# 1_-Power.net
KiCad netlist of a schematic drawn in Altium Designer
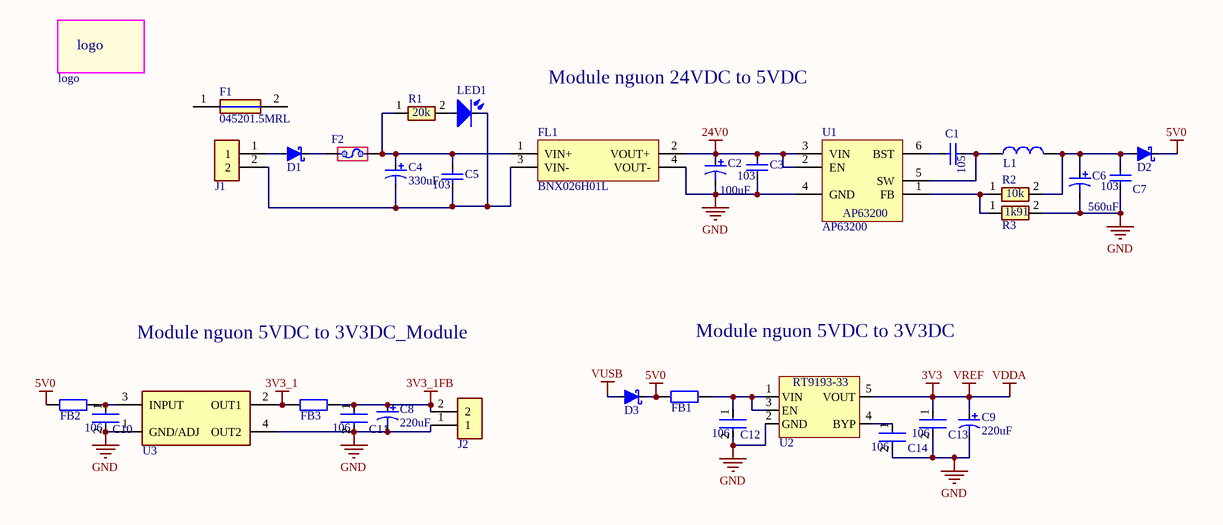
[diagram p0: [1]-Power.SchDoc]

(export (version "E")
  (design (tool "Eeschema 10.0.6"))
  (components
    (comp (ref "1")
      (value "logo")
      (footprint "SamacSys:logo_new_10mm")
      (libsource (lib "SamacSys") (part "logo"))
    )
    (comp (ref "C1")
      (value "C0603_105_50V")
      (footprint "SamacSys:C0603")
      (description "Multilayer Ceramic Capacitors MLCC - SMD/SMT 50 V 1uF X7R 0603 10%")
      (fields
        (field (name "MANUFACTURER_PART_NUMBER") "CC0603KRX7R9BB105")
        (field (name "MOUSER PART NUMBER") "603-CC603KRX7R9BB105")
      )
      (libsource (lib "SamacSys") (part "C0603_105_50V"))
    )
    (comp (ref "C2")
      (value "100uF")
      (footprint "SamacSys:CAP_ALUM_6_5x6_5")
      (description "Capacitor Polarised")
      (fields
        (field (name "MANUFACTURER_PART_NUMBER") "EEH-ZK1V101XP")
        (field (name "MOUSER PART NUMBER") "667-EEH-ZK1V101XP")
      )
      (libsource (lib "SamacSys") (part "C_Al_100uF_35V"))
    )
    (comp (ref "C3")
      (value "C0603_103_50V")
      (footprint "SamacSys:C0603")
      (description "Multilayer Ceramic Capacitors MLCC - SMD/SMT 50V 0.01uF X7R 0603 10%")
      (fields
        (field (name "MANUFACTURER_PART_NUMBER") "CC0603KRX7R9BB103")
        (field (name "MOUSER PART NUMBER") "603-CC603KRX7R9BB103")
      )
      (libsource (lib "SamacSys") (part "C0603_103_50V"))
    )
    (comp (ref "C4")
      (value "330uF")
      (footprint "CAP_ALUM_10X10")
      (description "Aluminum Organic Polymer Capacitors 35Vol 330uF SMD 2KHr ESR=22 mOhms AECQ200")
      (fields
        (field (name "MANUFACTURER_PART_NUMBER") "A768MS337M1VLAS022")
        (field (name "MOUSER PART NUMBER") "80-A768MS337M1VLAS22")
      )
      (libsource (lib "SamacSys") (part "C_Al_330uF_35V"))
    )
    (comp (ref "C5")
      (value "C0603_103_50V")
      (footprint "SamacSys:C0603")
      (description "Multilayer Ceramic Capacitors MLCC - SMD/SMT 50V 0.01uF X7R 0603 10%")
      (fields
        (field (name "MANUFACTURER_PART_NUMBER") "CC0603KRX7R9BB103")
        (field (name "MOUSER PART NUMBER") "603-CC603KRX7R9BB103")
      )
      (libsource (lib "SamacSys") (part "C0603_103_50V"))
    )
    (comp (ref "C6")
      (value "560uF")
      (footprint "SamacSys:CAP_ALUM_6_5x6_5")
      (description "560 µF 6.3 V Aluminum - Polymer Capacitors Radial, Can - SMD 8mOhm 15000 Hrs @ 105°C")
      (fields
        (field (name "MANUFACTURER") "United Chemi-Con")
        (field (name "PART NUMBER") "APXJ6R3ARA561MF80G")
      )
      (libsource (lib "SamacSys") (part "CAP_ALU6.3_560uF_6.3V"))
    )
    (comp (ref "C7")
      (value "C0603_103_50V")
      (footprint "SamacSys:C0603")
      (description "Multilayer Ceramic Capacitors MLCC - SMD/SMT 50V 0.01uF X7R 0603 10%")
      (fields
        (field (name "MANUFACTURER_PART_NUMBER") "CC0603KRX7R9BB103")
        (field (name "MOUSER PART NUMBER") "603-CC603KRX7R9BB103")
      )
      (libsource (lib "SamacSys") (part "C0603_103_50V"))
    )
    (comp (ref "C8")
      (value "220uF")
      (footprint "SamacSys:CAP_TAN_7343")
      (description "220 µF Molded Tantalum Capacitors 16 V 2917 (7343 Metric) 25mOhm")
      (fields (field (name "MANUFACTURER") "KYOCERA AVX") (field (name "PART NUMBER") "TPME227K016R0025"))
      (libsource (lib "SamacSys") (part "CAP_TAN_7343_220uF_16V"))
    )
    (comp (ref "C9")
      (value "220uF")
      (footprint "SamacSys:CAP_TAN_7343")
      (description "220 µF Molded Tantalum Capacitors 16 V 2917 (7343 Metric) 25mOhm")
      (fields (field (name "MANUFACTURER") "KYOCERA AVX") (field (name "PART NUMBER") "TPME227K016R0025"))
      (libsource (lib "SamacSys") (part "CAP_TAN_7343_220uF_16V"))
    )
    (comp (ref "C10")
      (value "C0603_106_35V")
      (footprint "SamacSys:C0603")
      (description "Multilayer Ceramic Capacitors MLCC - SMD/SMT 10 uF 35 VDC 20% 0603 X5R")
      (fields
        (field (name "MANUFACTURER_PART_NUMBER") "GRM188R6YA106MA73J")
        (field (name "MOUSER PART NUMBER") "81-GRM188R6YA106MA3J")
      )
      (libsource (lib "SamacSys") (part "C0603_106_35V"))
    )
    (comp (ref "C11")
      (value "C0603_106_35V")
      (footprint "SamacSys:C0603")
      (description "Multilayer Ceramic Capacitors MLCC - SMD/SMT 10 uF 35 VDC 20% 0603 X5R")
      (fields
        (field (name "MANUFACTURER_PART_NUMBER") "GRM188R6YA106MA73J")
        (field (name "MOUSER PART NUMBER") "81-GRM188R6YA106MA3J")
      )
      (libsource (lib "SamacSys") (part "C0603_106_35V"))
    )
    (comp (ref "C12")
      (value "C0603_106_35V")
      (footprint "SamacSys:C0603")
      (description "Multilayer Ceramic Capacitors MLCC - SMD/SMT 10 uF 35 VDC 20% 0603 X5R")
      (fields
        (field (name "MANUFACTURER_PART_NUMBER") "GRM188R6YA106MA73J")
        (field (name "MOUSER PART NUMBER") "81-GRM188R6YA106MA3J")
      )
      (libsource (lib "SamacSys") (part "C0603_106_35V"))
    )
    (comp (ref "C13")
      (value "C0603_106_35V")
      (footprint "SamacSys:C0603")
      (description "Multilayer Ceramic Capacitors MLCC - SMD/SMT 10 uF 35 VDC 20% 0603 X5R")
      (fields
        (field (name "MANUFACTURER_PART_NUMBER") "GRM188R6YA106MA73J")
        (field (name "MOUSER PART NUMBER") "81-GRM188R6YA106MA3J")
      )
      (libsource (lib "SamacSys") (part "C0603_106_35V"))
    )
    (comp (ref "C14")
      (value "C0603_106_35V")
      (footprint "SamacSys:C0603")
      (description "Multilayer Ceramic Capacitors MLCC - SMD/SMT 10 uF 35 VDC 20% 0603 X5R")
      (fields
        (field (name "MANUFACTURER_PART_NUMBER") "GRM188R6YA106MA73J")
        (field (name "MOUSER PART NUMBER") "81-GRM188R6YA106MA3J")
      )
      (libsource (lib "SamacSys") (part "C0603_106_35V"))
    )
    (comp (ref "D1")
      (value "PMEG40T30ERX")
      (footprint "SamacSys:SOD123")
      (description "Schottky Diode 40V 3A")
      (fields (field (name "MOUSER PART NUMBER") "771-PMEG40T30ERX"))
      (libsource (lib "SamacSys") (part "PMEG40T30ERX"))
    )
    (comp (ref "D2")
      (value "PMEG40T30ERX")
      (footprint "SamacSys:SOD123")
      (description "Schottky Diode 40V 3A")
      (fields (field (name "MOUSER PART NUMBER") "771-PMEG40T30ERX"))
      (libsource (lib "SamacSys") (part "PMEG40T30ERX"))
    )
    (comp (ref "D3")
      (value "PMEG40T30ERX")
      (footprint "SamacSys:SOD123")
      (description "Schottky Diode 40V 3A")
      (fields (field (name "MOUSER PART NUMBER") "771-PMEG40T30ERX"))
      (libsource (lib "SamacSys") (part "PMEG40T30ERX"))
    )
    (comp (ref "F1")
      (value "045201.5MRL")
      (description "Fuse")
      (fields (field (name "MOUSER PART NUMBER") "576-045201.5MRL"))
      (libsource (lib "SamacSys") (part "045201.5MRL"))
    )
    (comp (ref "F2")
      (value "01550900M")
      (footprint "SamacSys:FUSE_HOLDER_SMD")
      (description "Fuse holder")
      (fields (field (name "MOUSER PART NUMBER") "576-01550900M"))
      (libsource (lib "SamacSys") (part "01550900M"))
    )
    (comp (ref "FB1")
      (value "FERRIT_0805_1A")
      (footprint "SamacSys:FB0805")
      (fields
        (field (name "MANUFACTURER") "Laird-Signal Integrity Products")
        (field (name "PART NUMBER") "MI0805J102R-10")
      )
      (libsource (lib "SamacSys") (part "FERRIT_0805_1A"))
    )
    (comp (ref "FB2")
      (value "FERRIT_0805_1A")
      (footprint "SamacSys:FB0805")
      (fields
        (field (name "MANUFACTURER") "Laird-Signal Integrity Products")
        (field (name "PART NUMBER") "MI0805J102R-10")
      )
      (libsource (lib "SamacSys") (part "FERRIT_0805_1A"))
    )
    (comp (ref "FB3")
      (value "FERRIT_0805_1A")
      (footprint "SamacSys:FB0805")
      (fields
        (field (name "MANUFACTURER") "Laird-Signal Integrity Products")
        (field (name "PART NUMBER") "MI0805J102R-10")
      )
      (libsource (lib "SamacSys") (part "FERRIT_0805_1A"))
    )
    (comp (ref "FL1")
      (value "BNX026H01L")
      (footprint "SamacSys:BNX024")
      (description "Filter")
      (fields (field (name "MOUSER PART NUMBER") "81-BNX026H01L"))
      (libsource (lib "SamacSys") (part "BNX026H01L"))
    )
    (comp (ref "J1")
      (value "Terminal_2P_5.08mm")
      (footprint "SamacSys:1729128")
      (description "Fixed Terminal Blocks 2P 5.08mm 90DEG")
      (fields
        (field (name "MANUFACTURER_PART_NUMBER") "1729128")
        (field (name "MOUSER PART NUMBER") "651-1729128")
      )
      (libsource (lib "SamacSys") (part "Terminal_2P_5.08mm"))
    )
    (comp (ref "J2")
      (value "Terminal_2P_5.08mm")
      (footprint "SamacSys:1729128")
      (description "Fixed Terminal Blocks 2P 5.08mm 90DEG")
      (fields
        (field (name "MANUFACTURER_PART_NUMBER") "1729128")
        (field (name "MOUSER PART NUMBER") "651-1729128")
      )
      (libsource (lib "") (part "Terminal_2P_5.08mm_1"))
    )
    (comp (ref "L1")
      (value "IND_4.7U_1.82A_4.5X4.0")
      (footprint "SamacSys:IND_4.5x4")
      (fields (field (name "MANUFACTURER") "Würth Elektronik") (field (name "PART NUMBER") "744773047"))
      (libsource (lib "SamacSys") (part "IND_4.7U_1.82A_4.5X4.0"))
    )
    (comp (ref "LED1")
      (value "LED0603_Blue")
      (footprint "SamacSys:LED0603")
      (description "Blue 470nm LED Indication - Discrete 3.2V 0603 (1608 Metric)")
      (fields
        (field (name "MANUFACTURER_PART_NUMBER") "150060BS75000")
        (field (name "MOUSER PART NUMBER") "710-150060BS75000")
      )
      (libsource (lib "SamacSys") (part "LED0603_Blue"))
    )
    (comp (ref "R1")
      (value "R0603_20k")
      (footprint "RES-SMD-0603")
      (description "Resistor")
      (fields
        (field (name "MANUFACTURER_PART_NUMBER") "ERJ-3EKF2002V")
        (field (name "MOUSER PART NUMBER") "667-ERJ-3EKF2002V")
      )
      (libsource (lib "SamacSys") (part "R0603_20k"))
    )
    (comp (ref "R2")
      (value "R0603_10k")
      (footprint "SamacSys:RES-SMD-0603")
      (description "Thick Film Resistors - SMD 0603 10Kohms 1% AEC-Q200")
      (fields
        (field (name "MANUFACTURER_PART_NUMBER") "ERJ-3EKF1002V")
        (field (name "MOUSER PART NUMBER") "667-ERJ-3EKF1002V")
      )
      (libsource (lib "SamacSys") (part "R0603_10k"))
    )
    (comp (ref "R3")
      (value "R0603_1k91")
      (footprint "RES-SMD-0603")
      (description "Resistor")
      (fields
        (field (name "MANUFACTURER_PART_NUMBER") "ERJ-3EKF1911V")
        (field (name "MOUSER PART NUMBER") "667-ERJ-3EKF1911V")
      )
      (libsource (lib "SamacSys") (part "R0603_1k91"))
    )
    (comp (ref "U1")
      (value "AP63200")
      (footprint "SOT-23-6")
      (description "Buck Switching Regulator IC Positive Adjustable 1.2V 1 Output 2A SOT-23-6 Thin, TSOT-23-6")
      (fields (field (name "MANUFACTURER") "Diodes Incorporated") (field (name "PART NUMBER") "AP63200WU-7"))
      (libsource (lib "SamacSys") (part "AP63200"))
    )
    (comp (ref "U2")
      (value "RT9193-33GB")
      (footprint "SOT-23-5")
      (description "Linear Voltage Regulator IC Positive Fixed 1 Output 300mA SOT-23-5")
      (fields (field (name "MANUFACTURER") "Richtek USA Inc."))
      (libsource (lib "SamacSys") (part "RT9193-33GB"))
    )
    (comp (ref "U3")
      (value "NCP1117ST33T3G")
      (footprint "SamacSys:SOT230P700X180-4N")
      (description "LDO Voltage Regulators 3.3V 1A Positive")
      (fields (field (name "MOUSER PART NUMBER") "863-NCP1117ST33T3G"))
      (libsource (lib "SamacSys") (part "NCP1117ST33T3G"))
    )
  )
  (nets
    (net (code "1") (name "3V3") (class "Default")
      (node (ref "C13") (pin "1") (pinfunction "1_1") (pintype "passive"))
      (node (ref "C9") (pin "1") (pinfunction "1_1") (pintype "passive"))
      (node (ref "U2") (pin "5") (pinfunction "VOUT_5") (pintype "passive"))
    )
    (net (code "2") (name "3V3_1") (class "Default")
      (node (ref "FB3") (pin "1") (pinfunction "1_1") (pintype "passive"))
      (node (ref "U3") (pin "2") (pinfunction "OUT1_2") (pintype "passive"))
    )
    (net (code "3") (name "3V3_1FB") (class "Default")
      (node (ref "C11") (pin "1") (pinfunction "1_1") (pintype "passive"))
      (node (ref "C8") (pin "1") (pinfunction "1_1") (pintype "passive"))
      (node (ref "FB3") (pin "2") (pinfunction "2_2") (pintype "passive"))
      (node (ref "J2") (pin "2") (pinfunction "2_2") (pintype "passive"))
    )
    (net (code "4") (name "5V0") (class "Default")
      (node (ref "D2") (pin "2") (pinfunction "K_2") (pintype "passive"))
      (node (ref "D3") (pin "2") (pinfunction "K_2") (pintype "passive"))
      (node (ref "FB1") (pin "1") (pinfunction "1_1") (pintype "passive"))
      (node (ref "FB2") (pin "1") (pinfunction "1_1") (pintype "passive"))
    )
    (net (code "5") (name "24V0") (class "Default")
      (node (ref "C2") (pin "1") (pinfunction "1_1") (pintype "passive"))
      (node (ref "C3") (pin "1") (pinfunction "1_1") (pintype "passive"))
      (node (ref "FL1") (pin "2") (pinfunction "VOUT+_2") (pintype "power_in"))
      (node (ref "U1") (pin "2") (pinfunction "EN_2") (pintype "passive"))
      (node (ref "U1") (pin "3") (pinfunction "VIN_3") (pintype "passive"))
    )
    (net (code "6") (name "GND") (class "Default")
      (node (ref "C10") (pin "2") (pinfunction "2_2") (pintype "passive"))
      (node (ref "C11") (pin "2") (pinfunction "2_2") (pintype "passive"))
      (node (ref "C12") (pin "2") (pinfunction "2_2") (pintype "passive"))
      (node (ref "C13") (pin "2") (pinfunction "2_2") (pintype "passive"))
      (node (ref "C14") (pin "2") (pinfunction "2_2") (pintype "passive"))
      (node (ref "C2") (pin "2") (pinfunction "2_2") (pintype "passive"))
      (node (ref "C3") (pin "2") (pinfunction "2_2") (pintype "passive"))
      (node (ref "C6") (pin "2") (pinfunction "2_2") (pintype "passive"))
      (node (ref "C7") (pin "2") (pinfunction "2_2") (pintype "passive"))
      (node (ref "C8") (pin "2") (pinfunction "2_2") (pintype "passive"))
      (node (ref "C9") (pin "2") (pinfunction "2_2") (pintype "passive"))
      (node (ref "FL1") (pin "4") (pinfunction "VOUT-_4") (pintype "power_in"))
      (node (ref "J2") (pin "1") (pinfunction "1_1") (pintype "passive"))
      (node (ref "R3") (pin "2") (pinfunction "2_2") (pintype "passive"))
      (node (ref "U1") (pin "4") (pinfunction "GND_4") (pintype "passive"))
      (node (ref "U2") (pin "2") (pinfunction "GND_2") (pintype "passive"))
      (node (ref "U3") (pin "1") (pinfunction "GND/ADJ_1") (pintype "passive"))
      (node (ref "U3") (pin "4") (pinfunction "OUT2_4") (pintype "passive"))
    )
    (net (code "7") (name "Net-(D1-A)") (class "Default")
      (node (ref "D1") (pin "1") (pinfunction "A_1") (pintype "passive"))
      (node (ref "J1") (pin "1") (pinfunction "1_1") (pintype "passive"))
    )
    (net (code "8") (name "Net-(D1-K)") (class "Default")
      (node (ref "D1") (pin "2") (pinfunction "K_2") (pintype "passive"))
      (node (ref "F2") (pin "1") (pinfunction "1_1") (pintype "power_in"))
    )
    (net (code "9") (name "Net-(D2-A)") (class "Default")
      (node (ref "C6") (pin "1") (pinfunction "1_1") (pintype "passive"))
      (node (ref "C7") (pin "1") (pinfunction "1_1") (pintype "passive"))
      (node (ref "D2") (pin "1") (pinfunction "A_1") (pintype "passive"))
      (node (ref "L1") (pin "2") (pinfunction "2_2") (pintype "passive"))
      (node (ref "R2") (pin "2") (pinfunction "2_2") (pintype "passive"))
    )
    (net (code "10") (name "Net-(FL1-VIN+)") (class "Default")
      (node (ref "C4") (pin "1") (pinfunction "1_1") (pintype "passive"))
      (node (ref "C5") (pin "1") (pinfunction "1_1") (pintype "passive"))
      (node (ref "F2") (pin "2") (pinfunction "2_2") (pintype "power_in"))
      (node (ref "FL1") (pin "1") (pinfunction "VIN+_1") (pintype "passive"))
      (node (ref "R1") (pin "1") (pinfunction "1_1") (pintype "passive"))
    )
    (net (code "11") (name "Net-(FL1-VIN-)") (class "Default")
      (node (ref "C4") (pin "2") (pinfunction "2_2") (pintype "passive"))
      (node (ref "C5") (pin "2") (pinfunction "2_2") (pintype "passive"))
      (node (ref "FL1") (pin "3") (pinfunction "VIN-_3") (pintype "power_in"))
      (node (ref "J1") (pin "2") (pinfunction "2_2") (pintype "passive"))
      (node (ref "LED1") (pin "1") (pinfunction "K_1") (pintype "passive"))
    )
    (net (code "12") (name "Net-(LED1-A)") (class "Default")
      (node (ref "LED1") (pin "2") (pinfunction "A_2") (pintype "passive"))
      (node (ref "R1") (pin "2") (pinfunction "2_2") (pintype "passive"))
    )
    (net (code "13") (name "Net-(U1-BST)") (class "Default")
      (node (ref "C1") (pin "1") (pinfunction "1_1") (pintype "passive"))
      (node (ref "U1") (pin "6") (pinfunction "BST_6") (pintype "passive"))
    )
    (net (code "14") (name "Net-(U1-FB)") (class "Default")
      (node (ref "R2") (pin "1") (pinfunction "1_1") (pintype "passive"))
      (node (ref "R3") (pin "1") (pinfunction "1_1") (pintype "passive"))
      (node (ref "U1") (pin "1") (pinfunction "FB_1") (pintype "passive"))
    )
    (net (code "15") (name "Net-(U1-SW)") (class "Default")
      (node (ref "C1") (pin "2") (pinfunction "2_2") (pintype "passive"))
      (node (ref "L1") (pin "1") (pinfunction "1_1") (pintype "passive"))
      (node (ref "U1") (pin "5") (pinfunction "SW_5") (pintype "passive"))
    )
    (net (code "16") (name "Net-(U2-BYP)") (class "Default")
      (node (ref "C14") (pin "1") (pinfunction "1_1") (pintype "passive"))
      (node (ref "U2") (pin "4") (pinfunction "BYP_4") (pintype "passive"))
    )
    (net (code "17") (name "Net-(U2-EN)") (class "Default")
      (node (ref "C12") (pin "1") (pinfunction "1_1") (pintype "passive"))
      (node (ref "FB1") (pin "2") (pinfunction "2_2") (pintype "passive"))
      (node (ref "U2") (pin "1") (pinfunction "VIN_1") (pintype "passive"))
      (node (ref "U2") (pin "3") (pinfunction "EN_3") (pintype "passive"))
    )
    (net (code "18") (name "Net-(U3-INPUT)") (class "Default")
      (node (ref "C10") (pin "1") (pinfunction "1_1") (pintype "passive"))
      (node (ref "FB2") (pin "2") (pinfunction "2_2") (pintype "passive"))
      (node (ref "U3") (pin "3") (pinfunction "INPUT_3") (pintype "passive"))
    )
    (net (code "19") (name "VUSB") (class "Default")
      (node (ref "D3") (pin "1") (pinfunction "A_1") (pintype "passive"))
    )
    (net (code "20") (name "unconnected-(F1-Pad1)") (class "Default")
      (node (ref "F1") (pin "1") (pinfunction "1_1") (pintype "passive"))
    )
    (net (code "21") (name "unconnected-(F1-Pad2)") (class "Default")
      (node (ref "F1") (pin "2") (pinfunction "2_2") (pintype "passive"))
    )
  )
)
